# SAU-G0-EX_MAX31865.net
KiCad netlist of a schematic drawn in Altium Designer
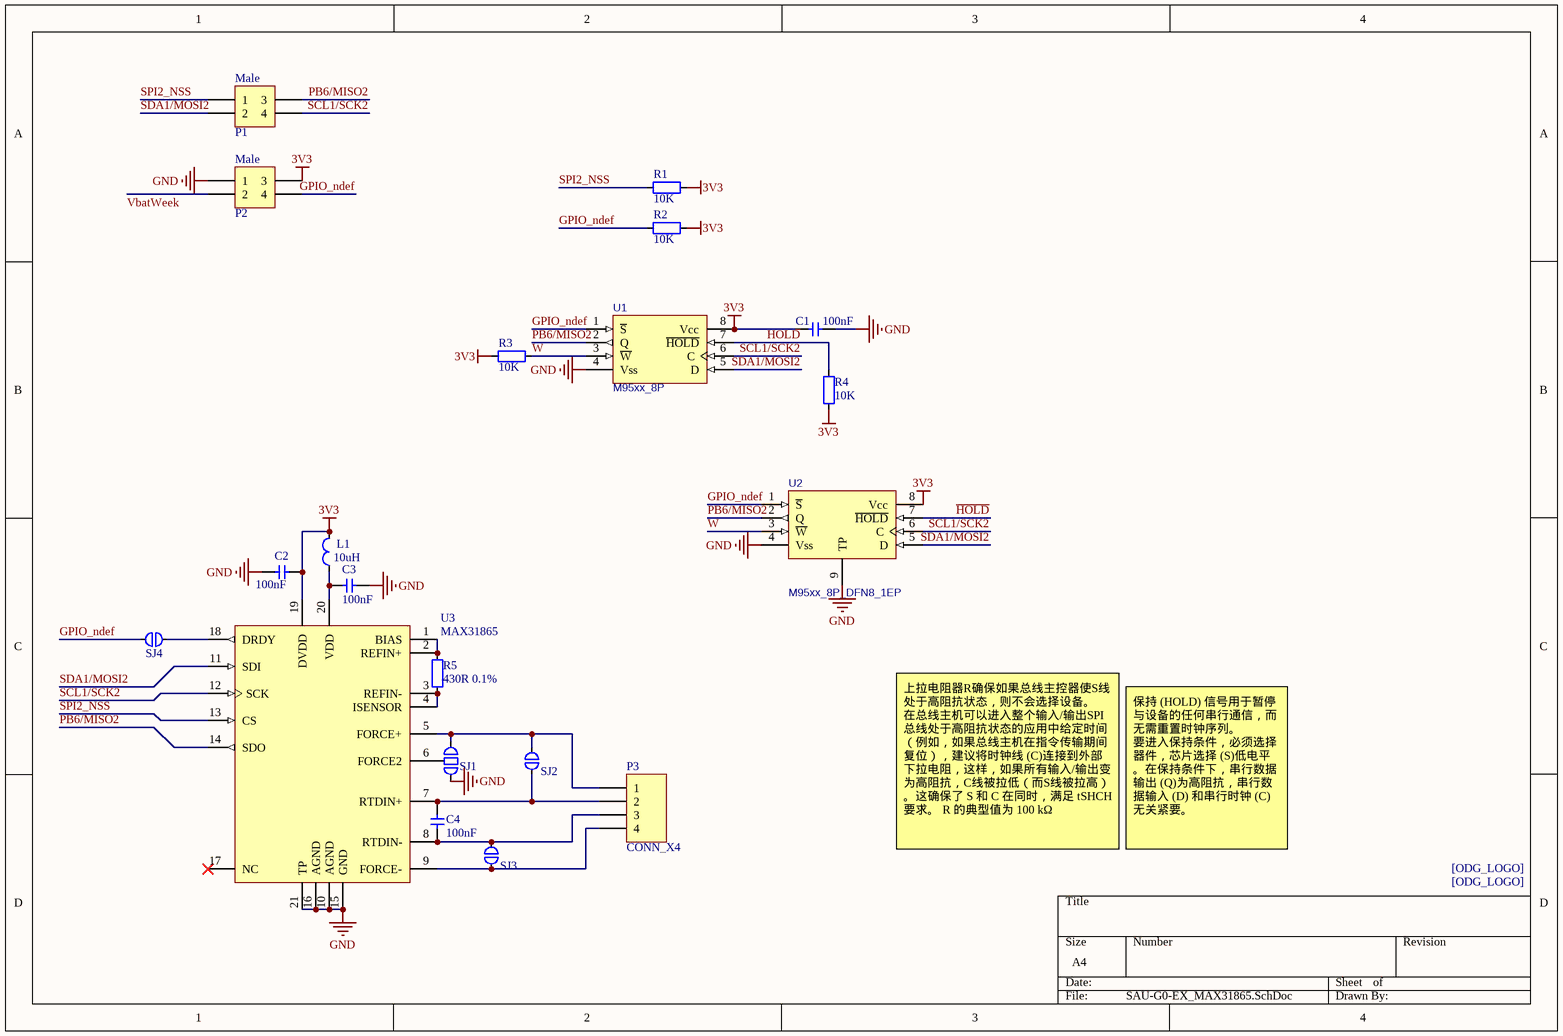
[diagram p0: SAU-G0-EX_MAX31865.SchDoc]

(export (version "E")
  (design (tool "Eeschema 10.0.6"))
  (components
    (comp (ref "C1")
      (value "100nF")
      (footprint "C0402")
      (description "Capacitor")
      (libsource (lib "ODG_AD_Lib") (part "CAP"))
    )
    (comp (ref "C2")
      (value "100nF")
      (footprint "C0402")
      (description "Capacitor")
      (libsource (lib "ODG_AD_Lib") (part "CAP"))
    )
    (comp (ref "C3")
      (value "100nF")
      (footprint "C0402")
      (description "Capacitor")
      (libsource (lib "ODG_AD_Lib") (part "CAP"))
    )
    (comp (ref "C4")
      (value "100nF")
      (footprint "C0402")
      (description "Capacitor")
      (libsource (lib "ODG_AD_Lib") (part "CAP"))
    )
    (comp (ref "L1")
      (value "10uH")
      (footprint "FER0603")
      (description "贴片叠层电感")
      (libsource (lib "ODG_AD_Lib") (part "inductor_mini"))
    )
    (comp (ref "ODG1")
      (value "ODG_LOGO")
      (footprint "ODG_LOGO_soldermask")
      (libsource (lib "ODG_AD_Lib") (part "ODG_LOGO"))
    )
    (comp (ref "ODG2")
      (value "ODG_LOGO")
      (footprint "ODG_LOGO_soldermask")
      (libsource (lib "ODG_AD_Lib") (part "ODG_LOGO"))
    )
    (comp (ref "P1")
      (value "Male")
      (footprint "2.0mm_Male_2x2")
      (libsource (lib "ODG_AD_Lib") (part "CONN_2X2"))
    )
    (comp (ref "P2")
      (value "Male")
      (footprint "2.0mm_Male_2x2")
      (libsource (lib "ODG_AD_Lib") (part "CONN_2X2"))
    )
    (comp (ref "P3")
      (value "CONN_X4")
      (footprint "2.54mm_Male_x4")
      (libsource (lib "ODG_AD_Lib") (part "CONN_X4"))
    )
    (comp (ref "R1")
      (value "10K")
      (footprint "R0402")
      (description "Resistor")
      (libsource (lib "") (part "RES_2"))
    )
    (comp (ref "R2")
      (value "10K")
      (footprint "R0402")
      (description "Resistor")
      (libsource (lib "") (part "RES_2"))
    )
    (comp (ref "R3")
      (value "10K")
      (footprint "R0402")
      (description "Resistor")
      (libsource (lib "") (part "RES_3"))
    )
    (comp (ref "R4")
      (value "10K")
      (footprint "R0402")
      (description "Resistor")
      (libsource (lib "ODG_AD_Lib") (part "RES"))
    )
    (comp (ref "R5")
      (value "430R 0.1%")
      (footprint "R0603")
      (description "Resistor")
      (libsource (lib "") (part "RES_1"))
    )
    (comp (ref "SJ1")
      (value "SJ_3P")
      (footprint "SJ_3P")
      (description "焊接跳线二选一")
      (libsource (lib "ODG_AD_Lib") (part "SJ_3P"))
    )
    (comp (ref "SJ2")
      (value "SJ_2P")
      (footprint "SJ_2P")
      (description "焊接跳线")
      (libsource (lib "ODG_AD_Lib") (part "SJ_2P"))
    )
    (comp (ref "SJ3")
      (value "SJ_2P")
      (footprint "SJ_2P")
      (description "焊接跳线")
      (libsource (lib "ODG_AD_Lib") (part "SJ_2P"))
    )
    (comp (ref "SJ4")
      (value "SJ_2P")
      (footprint "SJ_2P")
      (description "焊接跳线")
      (libsource (lib "ODG_AD_Lib") (part "SJ_2P"))
    )
    (comp (ref "U1")
      (value "M95xx_8P")
      (footprint "ANALOG DEV SOIC-8 R8")
      (description "Serial SPI bus EEPROM with high-speed clock")
      (libsource (lib "ODG_AD_Lib") (part "M95xx_8P"))
    )
    (comp (ref "U2")
      (value "M95xx_8P_DFN8_1EP")
      (footprint "DFN-8-1EP_3x2mm_P0.5mm_EP1.75x1.45mm")
      (description "Serial SPI bus EEPROM with high-speed clock")
      (libsource (lib "ODG_AD_Lib") (part "M95xx_8P_DFN8_1EP"))
    )
    (comp (ref "U3")
      (value "MAX31865")
      (footprint "VQFN-20 5x5MM 0.65")
      (libsource (lib "ODG_AD_Lib") (part "MAX31865"))
    )
  )
  (nets
    (net (code "1") (name "/GPIO_ndef") (class "Default")
      (node (ref "P2") (pin "4") (pinfunction "4_4") (pintype "passive"))
      (node (ref "R2") (pin "1") (pinfunction "1_1") (pintype "passive"))
      (node (ref "SJ4") (pin "2") (pinfunction "2_2") (pintype "passive"))
      (node (ref "U1") (pin "1") (pinfunction "~{S}_1") (pintype "input"))
      (node (ref "U2") (pin "1") (pinfunction "~{S}_1") (pintype "input"))
    )
    (net (code "2") (name "/PB6{slash}MISO2") (class "Default")
      (node (ref "P1") (pin "3") (pinfunction "3_3") (pintype "passive"))
      (node (ref "U1") (pin "2") (pinfunction "Q_2") (pintype "output"))
      (node (ref "U2") (pin "2") (pinfunction "Q_2") (pintype "output"))
      (node (ref "U3") (pin "14") (pinfunction "SDO_14") (pintype "output"))
    )
    (net (code "3") (name "/SCL1{slash}SCK2") (class "Default")
      (node (ref "P1") (pin "4") (pinfunction "4_4") (pintype "passive"))
      (node (ref "U1") (pin "6") (pinfunction "C_6") (pintype "input"))
      (node (ref "U2") (pin "6") (pinfunction "C_6") (pintype "input"))
      (node (ref "U3") (pin "12") (pinfunction "SCK_12") (pintype "input"))
    )
    (net (code "4") (name "/SDA1{slash}MOSI2") (class "Default")
      (node (ref "P1") (pin "2") (pinfunction "2_2") (pintype "passive"))
      (node (ref "U1") (pin "5") (pinfunction "D_5") (pintype "input"))
      (node (ref "U2") (pin "5") (pinfunction "D_5") (pintype "input"))
      (node (ref "U3") (pin "11") (pinfunction "SDI_11") (pintype "input"))
    )
    (net (code "5") (name "/SPI2_NSS") (class "Default")
      (node (ref "P1") (pin "1") (pinfunction "1_1") (pintype "passive"))
      (node (ref "R1") (pin "1") (pinfunction "1_1") (pintype "passive"))
      (node (ref "U3") (pin "13") (pinfunction "CS_13") (pintype "input"))
    )
    (net (code "6") (name "/VbatWeek") (class "Default")
      (node (ref "P2") (pin "2") (pinfunction "2_2") (pintype "passive"))
    )
    (net (code "7") (name "/~{HOLD}") (class "Default")
      (node (ref "R4") (pin "1") (pinfunction "1_1") (pintype "passive"))
      (node (ref "U1") (pin "7") (pinfunction "~{HOLD}_7") (pintype "input"))
      (node (ref "U2") (pin "7") (pinfunction "~{HOLD}_7") (pintype "input"))
    )
    (net (code "8") (name "/~{W}") (class "Default")
      (node (ref "R3") (pin "1") (pinfunction "1_1") (pintype "passive"))
      (node (ref "U1") (pin "3") (pinfunction "~{W}_3") (pintype "input"))
      (node (ref "U2") (pin "3") (pinfunction "~{W}_3") (pintype "input"))
    )
    (net (code "9") (name "3V3") (class "Default")
      (node (ref "C1") (pin "2") (pinfunction "2_2") (pintype "passive"))
      (node (ref "C2") (pin "1") (pinfunction "1_1") (pintype "passive"))
      (node (ref "L1") (pin "2") (pinfunction "2_2") (pintype "passive"))
      (node (ref "P2") (pin "3") (pinfunction "3_3") (pintype "passive"))
      (node (ref "R1") (pin "2") (pinfunction "2_2") (pintype "passive"))
      (node (ref "R2") (pin "2") (pinfunction "2_2") (pintype "passive"))
      (node (ref "R3") (pin "2") (pinfunction "2_2") (pintype "passive"))
      (node (ref "R4") (pin "2") (pinfunction "2_2") (pintype "passive"))
      (node (ref "U1") (pin "8") (pinfunction "Vcc_8") (pintype "passive"))
      (node (ref "U2") (pin "8") (pinfunction "Vcc_8") (pintype "passive"))
      (node (ref "U3") (pin "19") (pinfunction "DVDD_19") (pintype "passive"))
    )
    (net (code "10") (name "GND") (class "Default")
      (node (ref "C1") (pin "1") (pinfunction "1_1") (pintype "passive"))
      (node (ref "C2") (pin "2") (pinfunction "2_2") (pintype "passive"))
      (node (ref "C3") (pin "2") (pinfunction "2_2") (pintype "passive"))
      (node (ref "P2") (pin "1") (pinfunction "1_1") (pintype "passive"))
      (node (ref "SJ1") (pin "3") (pinfunction "3_3") (pintype "passive"))
      (node (ref "U1") (pin "4") (pinfunction "Vss_4") (pintype "passive"))
      (node (ref "U2") (pin "4") (pinfunction "Vss_4") (pintype "passive"))
      (node (ref "U2") (pin "9") (pinfunction "TP_9") (pintype "passive"))
      (node (ref "U3") (pin "10") (pinfunction "AGND_10") (pintype "passive"))
      (node (ref "U3") (pin "15") (pinfunction "GND_15") (pintype "passive"))
      (node (ref "U3") (pin "16") (pinfunction "AGND_16") (pintype "passive"))
      (node (ref "U3") (pin "21") (pinfunction "TP_21") (pintype "passive"))
    )
    (net (code "11") (name "Net-(U3-BIAS)") (class "Default")
      (node (ref "R5") (pin "2") (pinfunction "2_2") (pintype "passive"))
      (node (ref "U3") (pin "1") (pinfunction "BIAS_1") (pintype "passive"))
      (node (ref "U3") (pin "2") (pinfunction "REFIN+_2") (pintype "passive"))
    )
    (net (code "12") (name "Net-(U3-DRDY)") (class "Default")
      (node (ref "SJ4") (pin "1") (pinfunction "1_1") (pintype "passive"))
      (node (ref "U3") (pin "18") (pinfunction "DRDY_18") (pintype "output"))
    )
    (net (code "13") (name "Net-(U3-FORCE+)") (class "Default")
      (node (ref "P3") (pin "1") (pinfunction "1_1") (pintype "passive"))
      (node (ref "SJ1") (pin "1") (pinfunction "1_1") (pintype "passive"))
      (node (ref "SJ2") (pin "1") (pinfunction "1_1") (pintype "passive"))
      (node (ref "U3") (pin "5") (pinfunction "FORCE+_5") (pintype "passive"))
    )
    (net (code "14") (name "Net-(U3-FORCE-)") (class "Default")
      (node (ref "P3") (pin "4") (pinfunction "4_4") (pintype "passive"))
      (node (ref "SJ3") (pin "2") (pinfunction "2_2") (pintype "passive"))
      (node (ref "U3") (pin "9") (pinfunction "FORCE-_9") (pintype "passive"))
    )
    (net (code "15") (name "Net-(U3-FORCE2)") (class "Default")
      (node (ref "SJ1") (pin "2") (pinfunction "2_2") (pintype "passive"))
      (node (ref "U3") (pin "6") (pinfunction "FORCE2_6") (pintype "passive"))
    )
    (net (code "16") (name "Net-(U3-ISENSOR)") (class "Default")
      (node (ref "R5") (pin "1") (pinfunction "1_1") (pintype "passive"))
      (node (ref "U3") (pin "3") (pinfunction "REFIN-_3") (pintype "passive"))
      (node (ref "U3") (pin "4") (pinfunction "ISENSOR_4") (pintype "passive"))
    )
    (net (code "17") (name "Net-(U3-RTDIN+)") (class "Default")
      (node (ref "C4") (pin "1") (pinfunction "1_1") (pintype "passive"))
      (node (ref "P3") (pin "2") (pinfunction "2_2") (pintype "passive"))
      (node (ref "SJ2") (pin "2") (pinfunction "2_2") (pintype "passive"))
      (node (ref "U3") (pin "7") (pinfunction "RTDIN+_7") (pintype "passive"))
    )
    (net (code "18") (name "Net-(U3-RTDIN-)") (class "Default")
      (node (ref "C4") (pin "2") (pinfunction "2_2") (pintype "passive"))
      (node (ref "P3") (pin "3") (pinfunction "3_3") (pintype "passive"))
      (node (ref "SJ3") (pin "1") (pinfunction "1_1") (pintype "passive"))
      (node (ref "U3") (pin "8") (pinfunction "RTDIN-_8") (pintype "passive"))
    )
    (net (code "19") (name "Net-(U3-VDD)") (class "Default")
      (node (ref "C3") (pin "1") (pinfunction "1_1") (pintype "passive"))
      (node (ref "L1") (pin "1") (pinfunction "1_1") (pintype "passive"))
      (node (ref "U3") (pin "20") (pinfunction "VDD_20") (pintype "passive"))
    )
    (net (code "20") (name "unconnected-(U3-NC-Pad17)") (class "Default")
      (node (ref "U3") (pin "17") (pinfunction "NC_17") (pintype "passive+no_connect"))
    )
  )
)
